# S1_Connections.net
KiCad netlist of a schematic drawn in Altium Designer
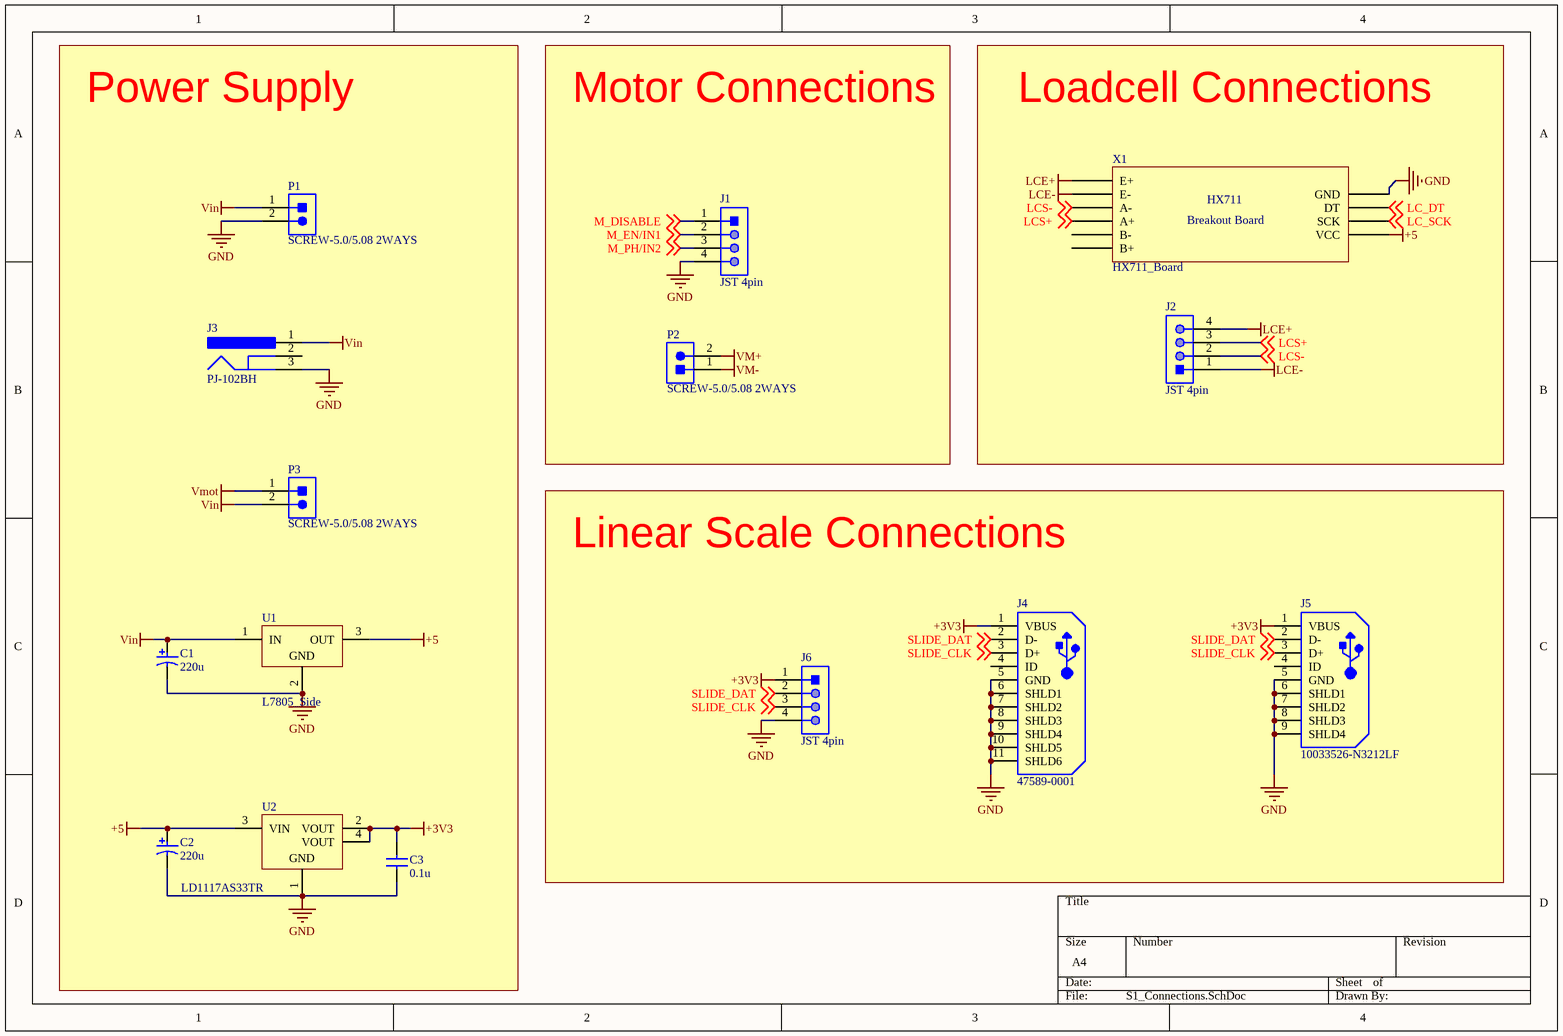
[diagram p0: S1_Connections.SchDoc]

(export (version "E")
  (design (tool "Eeschema 10.0.6"))
  (components
    (comp (ref "C1")
      (value "220u")
      (footprint "Alu Cap 6.3x2.5mm")
      (libsource (lib "Res and Cap") (part "Polar Cap"))
    )
    (comp (ref "C2")
      (value "220u")
      (footprint "Alu Cap 6.3x2.5mm")
      (libsource (lib "Res and Cap") (part "Polar Cap"))
    )
    (comp (ref "C3")
      (value "0.1u")
      (footprint "Ceramic Cap 5mm")
      (libsource (lib "Res and Cap") (part "Cap"))
    )
    (comp (ref "J1") (value "JST 4pin") (footprint "4Pin JST") (libsource (lib "Custom") (part "4Pin JST")))
    (comp (ref "J2") (value "JST 4pin") (footprint "4Pin JST") (libsource (lib "") (part "4Pin JST_1")))
    (comp (ref "J3")
      (value "PJ-102BH")
      (footprint "CUI-PJ-102BH_V")
      (fields (field (name "MANUFACTURER") "CUIInc."))
      (libsource (lib "Altium Content Vault") (part "JACK-2CD3-RN"))
    )
    (comp (ref "J4")
      (value "47589-0001")
      (footprint "MOLX-47589-0001_V")
      (description "Right Angle Female Type AB Micro USB Connector, 30 V, 1.8 A, -30 to 85 degC, RoHS, Tape and Reel")
      (fields (field (name "MANUFACTURER") "Molex"))
      (libsource (lib "Altium Content Vault") (part "USB-5-6SHLD"))
    )
    (comp (ref "J5")
      (value "10033526-N3212LF")
      (footprint "FCI-10033526-N3212LF_V")
      (description "Mini USB B-Type, 5-Pin SMD, RoHS, Tape and Reel")
      (fields (field (name "MANUFACTURER") "FCI"))
      (libsource (lib "Altium Content Vault") (part "USB-5-4SHLD"))
    )
    (comp (ref "J6") (value "JST 4pin") (footprint "4Pin JST") (libsource (lib "Custom") (part "4Pin JST")))
    (comp (ref "P1")
      (value "SCREW-5.0/5.08 2WAYS")
      (footprint "SCREW-5.0-2WAYS_V")
      (description "Socket, Screw Terminal Block, 2 Way, 5.0 mm Pitch, 90 Degree Angle, Through-Hole")
      (fields (field (name "MANUFACTURER") "No Vendor"))
      (libsource (lib "Altium Content Vault") (part "SCREW-2WAYS"))
    )
    (comp (ref "P2")
      (value "SCREW-5.0/5.08 2WAYS")
      (footprint "SCREW-5.0-2WAYS_V")
      (description "Socket, Screw Terminal Block, 2 Way, 5.0 mm Pitch, 90 Degree Angle, Through-Hole")
      (fields (field (name "MANUFACTURER") "No Vendor"))
      (libsource (lib "") (part "SCREW-2WAYS_1"))
    )
    (comp (ref "P3")
      (value "SCREW-5.0/5.08 2WAYS")
      (footprint "SCREW-5.0-2WAYS_V")
      (description "Socket, Screw Terminal Block, 2 Way, 5.0 mm Pitch, 90 Degree Angle, Through-Hole")
      (fields (field (name "MANUFACTURER") "No Vendor"))
      (libsource (lib "Altium Content Vault") (part "SCREW-2WAYS"))
    )
    (comp (ref "U1")
      (value "L7805_Side")
      (footprint "TO220_Side Mount")
      (libsource (lib "Custom") (part "L7805_Side"))
    )
    (comp (ref "U2")
      (value "LD1117AS33TR")
      (footprint "SOT-223_M")
      (description "1A, Low Drop Positive Voltage Regulator, 3.3V, 4-Pin SOT-223, Tape and Reel")
      (libsource (lib "Altium Content Vault") (part "PM-REG-LD1117-SOT4"))
    )
    (comp (ref "X1")
      (value "HX711_Board")
      (footprint "HX711_Board_Large")
      (libsource (lib "Custom") (part "HX711_Board"))
    )
  )
  (nets
    (net (code "1") (name "+3V3") (class "Default")
      (node (ref "C3") (pin "1") (pinfunction "1_1") (pintype "passive"))
      (node (ref "J4") (pin "1") (pinfunction "VBUS_1") (pintype "passive"))
      (node (ref "J5") (pin "1") (pinfunction "VBUS_1") (pintype "power_in"))
      (node (ref "J6") (pin "1") (pinfunction "1_1") (pintype "passive"))
      (node (ref "U2") (pin "2") (pinfunction "VOUT_2") (pintype "power_in"))
      (node (ref "U2") (pin "4") (pinfunction "VOUT_4") (pintype "power_in"))
    )
    (net (code "2") (name "+5") (class "Default")
      (node (ref "C2") (pin "1") (pinfunction "1_1") (pintype "passive"))
      (node (ref "U1") (pin "3") (pinfunction "OUT_3") (pintype "power_in"))
      (node (ref "U2") (pin "3") (pinfunction "VIN_3") (pintype "power_in"))
      (node (ref "X1") (pin "7") (pinfunction "VCC_7") (pintype "passive"))
    )
    (net (code "3") (name "GND") (class "Default")
      (node (ref "C1") (pin "2") (pinfunction "2_2") (pintype "passive"))
      (node (ref "C2") (pin "2") (pinfunction "2_2") (pintype "passive"))
      (node (ref "C3") (pin "2") (pinfunction "2_2") (pintype "passive"))
      (node (ref "J1") (pin "4") (pinfunction "4_4") (pintype "passive"))
      (node (ref "J3") (pin "3") (pinfunction "3_3") (pintype "passive"))
      (node (ref "J4") (pin "10") (pinfunction "SHLD5_10") (pintype "passive"))
      (node (ref "J4") (pin "11") (pinfunction "SHLD6_11") (pintype "passive"))
      (node (ref "J4") (pin "5") (pinfunction "GND_5") (pintype "passive"))
      (node (ref "J4") (pin "6") (pinfunction "SHLD1_6") (pintype "passive"))
      (node (ref "J4") (pin "7") (pinfunction "SHLD2_7") (pintype "passive"))
      (node (ref "J4") (pin "8") (pinfunction "SHLD3_8") (pintype "passive"))
      (node (ref "J4") (pin "9") (pinfunction "SHLD4_9") (pintype "passive"))
      (node (ref "J5") (pin "5") (pinfunction "GND_5") (pintype "power_in"))
      (node (ref "J5") (pin "6") (pinfunction "SHLD1_6") (pintype "passive"))
      (node (ref "J5") (pin "7") (pinfunction "SHLD2_7") (pintype "passive"))
      (node (ref "J5") (pin "8") (pinfunction "SHLD3_8") (pintype "passive"))
      (node (ref "J5") (pin "9") (pinfunction "SHLD4_9") (pintype "passive"))
      (node (ref "J6") (pin "4") (pinfunction "4_4") (pintype "passive"))
      (node (ref "P1") (pin "2") (pinfunction "2_2") (pintype "passive"))
      (node (ref "U1") (pin "2") (pinfunction "GND_2") (pintype "power_in"))
      (node (ref "U2") (pin "1") (pinfunction "GND_1") (pintype "power_in"))
      (node (ref "X1") (pin "10") (pinfunction "GND_10") (pintype "passive"))
    )
    (net (code "4") (name "LCE+") (class "Default")
      (node (ref "J2") (pin "4") (pinfunction "4_4") (pintype "passive"))
      (node (ref "X1") (pin "1") (pinfunction "E+_1") (pintype "passive"))
    )
    (net (code "5") (name "LCE-") (class "Default")
      (node (ref "J2") (pin "1") (pinfunction "1_1") (pintype "passive"))
      (node (ref "X1") (pin "2") (pinfunction "E-_2") (pintype "passive"))
    )
    (net (code "6") (name "LCS+") (class "Default")
      (node (ref "J2") (pin "3") (pinfunction "3_3") (pintype "passive"))
      (node (ref "X1") (pin "4") (pinfunction "A+_4") (pintype "passive"))
    )
    (net (code "7") (name "LCS-") (class "Default")
      (node (ref "J2") (pin "2") (pinfunction "2_2") (pintype "passive"))
      (node (ref "X1") (pin "3") (pinfunction "A-_3") (pintype "passive"))
    )
    (net (code "8") (name "LC_DT") (class "Default")
      (node (ref "X1") (pin "9") (pinfunction "DT_9") (pintype "passive"))
    )
    (net (code "9") (name "LC_SCK") (class "Default")
      (node (ref "X1") (pin "8") (pinfunction "SCK_8") (pintype "passive"))
    )
    (net (code "10") (name "M_DISABLE") (class "Default")
      (node (ref "J1") (pin "1") (pinfunction "1_1") (pintype "passive"))
    )
    (net (code "11") (name "M_EN{slash}IN1") (class "Default")
      (node (ref "J1") (pin "2") (pinfunction "2_2") (pintype "passive"))
    )
    (net (code "12") (name "M_PH{slash}IN2") (class "Default")
      (node (ref "J1") (pin "3") (pinfunction "3_3") (pintype "passive"))
    )
    (net (code "13") (name "SLIDE_CLK") (class "Default")
      (node (ref "J4") (pin "3") (pinfunction "D+_3") (pintype "passive"))
      (node (ref "J5") (pin "3") (pinfunction "D+_3") (pintype "passive"))
      (node (ref "J6") (pin "3") (pinfunction "3_3") (pintype "passive"))
    )
    (net (code "14") (name "SLIDE_DAT") (class "Default")
      (node (ref "J4") (pin "2") (pinfunction "D-_2") (pintype "passive"))
      (node (ref "J5") (pin "2") (pinfunction "D-_2") (pintype "passive"))
      (node (ref "J6") (pin "2") (pinfunction "2_2") (pintype "passive"))
    )
    (net (code "15") (name "VM+") (class "Default")
      (node (ref "P2") (pin "2") (pinfunction "2_2") (pintype "passive"))
    )
    (net (code "16") (name "VM-") (class "Default")
      (node (ref "P2") (pin "1") (pinfunction "1_1") (pintype "passive"))
    )
    (net (code "17") (name "Vin") (class "Default")
      (node (ref "C1") (pin "1") (pinfunction "1_1") (pintype "passive"))
      (node (ref "J3") (pin "1") (pinfunction "1_1") (pintype "passive"))
      (node (ref "P1") (pin "1") (pinfunction "1_1") (pintype "passive"))
      (node (ref "P3") (pin "2") (pinfunction "2_2") (pintype "passive"))
      (node (ref "U1") (pin "1") (pinfunction "IN_1") (pintype "power_in"))
    )
    (net (code "18") (name "Vmot") (class "Default")
      (node (ref "P3") (pin "1") (pinfunction "1_1") (pintype "passive"))
    )
    (net (code "19") (name "unconnected-(J3-Pad2)") (class "Default")
      (node (ref "J3") (pin "2") (pinfunction "2_2") (pintype "passive"))
    )
    (net (code "20") (name "unconnected-(J4-ID-Pad4)") (class "Default")
      (node (ref "J4") (pin "4") (pinfunction "ID_4") (pintype "passive"))
    )
    (net (code "21") (name "unconnected-(J5-ID-Pad4)") (class "Default")
      (node (ref "J5") (pin "4") (pinfunction "ID_4") (pintype "passive"))
    )
    (net (code "22") (name "unconnected-(X1-B+-Pad6)") (class "Default")
      (node (ref "X1") (pin "6") (pinfunction "B+_6") (pintype "passive"))
    )
    (net (code "23") (name "unconnected-(X1-B--Pad5)") (class "Default")
      (node (ref "X1") (pin "5") (pinfunction "B-_5") (pintype "passive"))
    )
  )
)
